# danger_danger_psu.net
KiCad netlist of a schematic drawn in EAGLE
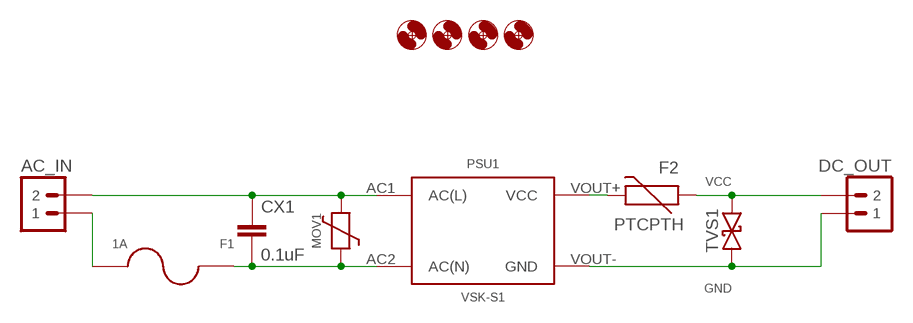
[diagram p0: schematic, sheet 1]

(export (version "E")
  (design (tool "Eeschema 10.0.6"))
  (components
    (comp (ref "AC_IN")
      (value "M025MM")
      (footprint "eagle-import:SCREWTERMINAL-5MM-2")
      (libsource (lib "eagle-import") (part "M025MM"))
    )
    (comp (ref "CX1")
      (value "0.1uF")
      (footprint "eagle-import:XC10B5")
      (libsource (lib "eagle-import") (part "CXXC10B5"))
    )
    (comp (ref "DC_OUT")
      (value "M02JST-PTH-VERT")
      (footprint "eagle-import:JST-2-PH-VERT-PTH")
      (libsource (lib "eagle-import") (part "M02JST-PTH-VERT"))
    )
    (comp (ref "F1")
      (value "1A")
      (footprint "eagle-import:FUSE-2AG")
      (libsource (lib "eagle-import") (part "FUSE5X20MM-2"))
    )
    (comp (ref "F2")
      (value "PTCPTH")
      (footprint "eagle-import:PTC")
      (libsource (lib "eagle-import") (part "PTCPTH"))
    )
    (comp (ref "H1")
      (value "HOLE#4")
      (footprint "eagle-import:HOLE-#4")
      (libsource (lib "eagle-import") (part "HOLE#4"))
    )
    (comp (ref "H2")
      (value "HOLE#4")
      (footprint "eagle-import:HOLE-#4")
      (libsource (lib "eagle-import") (part "HOLE#4"))
    )
    (comp (ref "H3")
      (value "HOLE#4")
      (footprint "eagle-import:HOLE-#4")
      (libsource (lib "eagle-import") (part "HOLE#4"))
    )
    (comp (ref "H4")
      (value "HOLE#4")
      (footprint "eagle-import:HOLE-#4")
      (libsource (lib "eagle-import") (part "HOLE#4"))
    )
    (comp (ref "MOV1")
      (value "VARISITORVAR-5.08MM-PTH")
      (footprint "eagle-import:VAR-5.08MM-PTH")
      (libsource (lib "eagle-import") (part "VARISITORVAR-5.08MM-PTH"))
    )
    (comp (ref "PSU1")
      (value "VSK-S1")
      (footprint "eagle-import:VSK-S1")
      (libsource (lib "eagle-import") (part "VSK-S1"))
    )
    (comp (ref "TVS1")
      (value "TVSDO-41-TVS-BIDIRECTIONAL")
      (footprint "eagle-import:DO-41-TVS")
      (libsource (lib "eagle-import") (part "TVSDO-41-TVS-BIDIRECTIONAL"))
    )
  )
  (nets
    (net (code "1") (name "/GND") (class "Default")
      (node (ref "DC_OUT") (pin "1") (pinfunction "1_1") (pintype "passive"))
      (node (ref "PSU1") (pin "VOUT-") (pinfunction "GND_VOUT-") (pintype "bidirectional"))
      (node (ref "TVS1") (pin "P$2") (pinfunction "2_P$2") (pintype "passive"))
    )
    (net (code "2") (name "/VCC") (class "Default")
      (node (ref "DC_OUT") (pin "2") (pinfunction "2_2") (pintype "passive"))
      (node (ref "F2") (pin "P$1") (pinfunction "1_P$1") (pintype "bidirectional"))
      (node (ref "TVS1") (pin "P$1") (pinfunction "1_P$1") (pintype "passive"))
    )
    (net (code "3") (name "Net-(AC_IN-Pad1)") (class "Default")
      (node (ref "AC_IN") (pin "1") (pinfunction "1_1") (pintype "passive"))
      (node (ref "F1") (pin "2") (pinfunction "2_2") (pintype "bidirectional"))
      (node (ref "F1") (pin "2@2") (pinfunction "2_2@2") (pintype "bidirectional"))
    )
    (net (code "4") (name "Net-(F2-2)") (class "Default")
      (node (ref "F2") (pin "P$2") (pinfunction "2_P$2") (pintype "bidirectional"))
      (node (ref "PSU1") (pin "VOUT+") (pinfunction "VCC_VOUT+") (pintype "bidirectional"))
    )
    (net (code "5") (name "Net-(MOV1-P$1)") (class "Default")
      (node (ref "CX1") (pin "2") (pinfunction "2_2") (pintype "passive"))
      (node (ref "F1") (pin "1") (pinfunction "1_1") (pintype "bidirectional"))
      (node (ref "F1") (pin "1@1") (pinfunction "1_1@1") (pintype "bidirectional"))
      (node (ref "MOV1") (pin "1") (pinfunction "P$1_1") (pintype "bidirectional"))
      (node (ref "PSU1") (pin "AC2") (pinfunction "AC(N)_AC2") (pintype "bidirectional"))
    )
    (net (code "6") (name "Net-(MOV1-P$2)") (class "Default")
      (node (ref "AC_IN") (pin "2") (pinfunction "2_2") (pintype "passive"))
      (node (ref "CX1") (pin "1") (pinfunction "1_1") (pintype "passive"))
      (node (ref "MOV1") (pin "2") (pinfunction "P$2_2") (pintype "bidirectional"))
      (node (ref "PSU1") (pin "AC1") (pinfunction "AC(L)_AC1") (pintype "bidirectional"))
    )
  )
)
